# ESP.net
KiCad netlist of a schematic drawn in Altium Designer
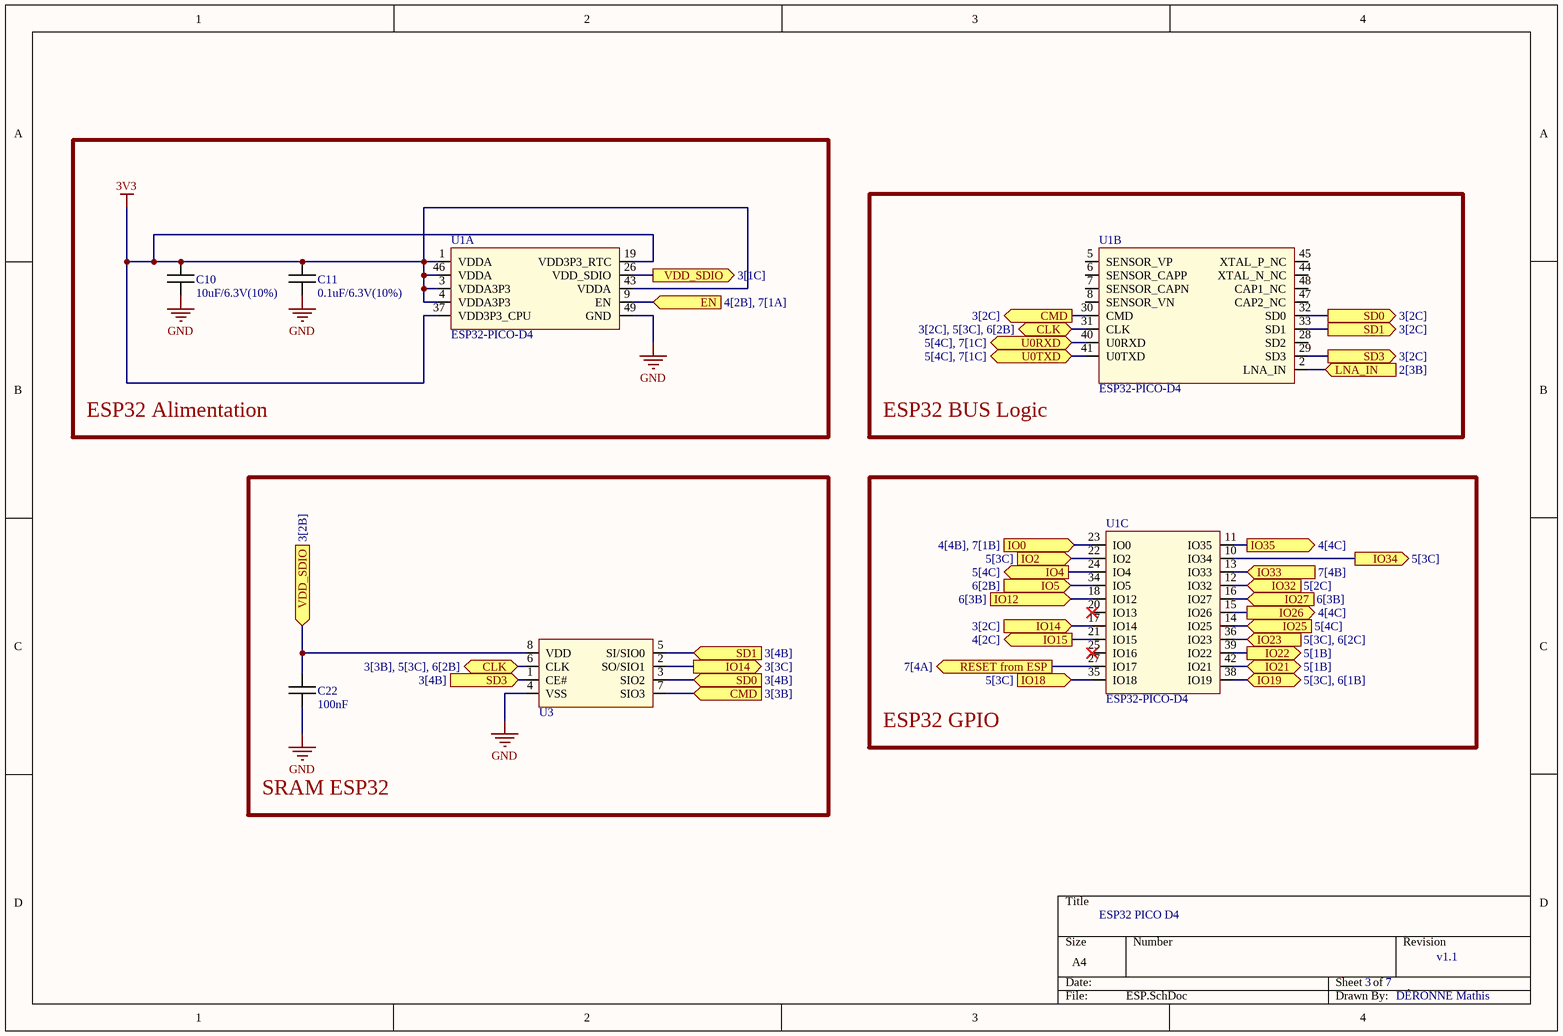
[diagram p0: ESP.SchDoc]

(export (version "E")
  (design (tool "Eeschema 10.0.6"))
  (components
    (comp (ref "C10")
      (value "10uF/6.3V(10%)")
      (footprint "CAPC1005X06N")
      (libsource (lib "SCHLibrary") (part "Capacitor"))
    )
    (comp (ref "C11")
      (value "0.1uF/6.3V(10%)")
      (footprint "CAPC1005X06N")
      (libsource (lib "SCHLibrary") (part "Capacitor"))
    )
    (comp (ref "C22")
      (value "100nF")
      (footprint "CAPC1005X06N")
      (libsource (lib "SCHLibrary") (part "Capacitor"))
    )
    (comp (ref "U1")
      (value "ESP32-PICO-D4")
      (footprint "PQFN50P700X700X104_HS-49N")
      (libsource (lib "SCHLibrary") (part "ESP32"))
    )
    (comp (ref "U3")
      (value "IS66WVS1M8BLL-104NLI")
      (footprint "SOIC127P600X175-8N")
      (description "SRAM 8Mb, SerialRAM, 2.7V-3.6V, 104MHz, 8 pin SOIC 150 mil, RoHS")
      (libsource (lib "SCHLibrary") (part "SRAM"))
    )
  )
  (nets
    (net (code "1") (name "/CLK") (class "Default")
      (node (ref "U1") (pin "31") (pinfunction "CLK_31") (pintype "passive"))
      (node (ref "U3") (pin "6") (pinfunction "CLK_6") (pintype "passive"))
    )
    (net (code "2") (name "/CMD") (class "Default")
      (node (ref "U1") (pin "30") (pinfunction "CMD_30") (pintype "passive"))
      (node (ref "U3") (pin "7") (pinfunction "SIO3_7") (pintype "passive"))
    )
    (net (code "3") (name "/EN") (class "Default")
      (node (ref "U1") (pin "9") (pinfunction "EN_9") (pintype "passive"))
    )
    (net (code "4") (name "/IO0") (class "Default")
      (node (ref "U1") (pin "23") (pinfunction "IO0_23") (pintype "passive"))
    )
    (net (code "5") (name "/IO2") (class "Default")
      (node (ref "U1") (pin "22") (pinfunction "IO2_22") (pintype "passive"))
    )
    (net (code "6") (name "/IO4") (class "Default")
      (node (ref "U1") (pin "24") (pinfunction "IO4_24") (pintype "passive"))
    )
    (net (code "7") (name "/IO5") (class "Default")
      (node (ref "U1") (pin "34") (pinfunction "IO5_34") (pintype "passive"))
    )
    (net (code "8") (name "/IO12") (class "Default")
      (node (ref "U1") (pin "18") (pinfunction "IO12_18") (pintype "passive"))
    )
    (net (code "9") (name "/IO14") (class "Default")
      (node (ref "U1") (pin "17") (pinfunction "IO14_17") (pintype "passive"))
      (node (ref "U3") (pin "2") (pinfunction "SO/SIO1_2") (pintype "passive"))
    )
    (net (code "10") (name "/IO15") (class "Default")
      (node (ref "U1") (pin "21") (pinfunction "IO15_21") (pintype "passive"))
    )
    (net (code "11") (name "/IO18") (class "Default")
      (node (ref "U1") (pin "35") (pinfunction "IO18_35") (pintype "passive"))
    )
    (net (code "12") (name "/IO19") (class "Default")
      (node (ref "U1") (pin "38") (pinfunction "IO19_38") (pintype "passive"))
    )
    (net (code "13") (name "/IO21") (class "Default")
      (node (ref "U1") (pin "42") (pinfunction "IO21_42") (pintype "passive"))
    )
    (net (code "14") (name "/IO22") (class "Default")
      (node (ref "U1") (pin "39") (pinfunction "IO22_39") (pintype "passive"))
    )
    (net (code "15") (name "/IO23") (class "Default")
      (node (ref "U1") (pin "36") (pinfunction "IO23_36") (pintype "passive"))
    )
    (net (code "16") (name "/IO25") (class "Default")
      (node (ref "U1") (pin "14") (pinfunction "IO25_14") (pintype "passive"))
    )
    (net (code "17") (name "/IO26") (class "Default")
      (node (ref "U1") (pin "15") (pinfunction "IO26_15") (pintype "passive"))
    )
    (net (code "18") (name "/IO27") (class "Default")
      (node (ref "U1") (pin "16") (pinfunction "IO27_16") (pintype "passive"))
    )
    (net (code "19") (name "/IO32") (class "Default")
      (node (ref "U1") (pin "12") (pinfunction "IO32_12") (pintype "passive"))
    )
    (net (code "20") (name "/IO33") (class "Default")
      (node (ref "U1") (pin "13") (pinfunction "IO33_13") (pintype "passive"))
    )
    (net (code "21") (name "/IO34") (class "Default")
      (node (ref "U1") (pin "10") (pinfunction "IO34_10") (pintype "passive"))
    )
    (net (code "22") (name "/IO35") (class "Default")
      (node (ref "U1") (pin "11") (pinfunction "IO35_11") (pintype "passive"))
    )
    (net (code "23") (name "/LNA_IN") (class "Default")
      (node (ref "U1") (pin "2") (pinfunction "LNA_IN_2") (pintype "passive"))
    )
    (net (code "24") (name "/RESET from ESP") (class "Default")
      (node (ref "U1") (pin "27") (pinfunction "IO17_27") (pintype "passive"))
    )
    (net (code "25") (name "/SD0") (class "Default")
      (node (ref "U1") (pin "32") (pinfunction "SD0_32") (pintype "passive"))
      (node (ref "U3") (pin "3") (pinfunction "SIO2_3") (pintype "passive"))
    )
    (net (code "26") (name "/SD1") (class "Default")
      (node (ref "U1") (pin "33") (pinfunction "SD1_33") (pintype "passive"))
      (node (ref "U3") (pin "5") (pinfunction "SI/SIO0_5") (pintype "passive"))
    )
    (net (code "27") (name "/SD3") (class "Default")
      (node (ref "U1") (pin "29") (pinfunction "SD3_29") (pintype "passive"))
      (node (ref "U3") (pin "1") (pinfunction "CE#_1") (pintype "passive"))
    )
    (net (code "28") (name "/U0RXD") (class "Default")
      (node (ref "U1") (pin "40") (pinfunction "U0RXD_40") (pintype "passive"))
    )
    (net (code "29") (name "/U0TXD") (class "Default")
      (node (ref "U1") (pin "41") (pinfunction "U0TXD_41") (pintype "passive"))
    )
    (net (code "30") (name "/VDD_SDIO") (class "Default")
      (node (ref "C22") (pin "1") (pinfunction "1_1") (pintype "passive"))
      (node (ref "U1") (pin "26") (pinfunction "VDD_SDIO_26") (pintype "passive"))
      (node (ref "U3") (pin "8") (pinfunction "VDD_8") (pintype "passive"))
    )
    (net (code "31") (name "3V3") (class "Default")
      (node (ref "C10") (pin "2") (pinfunction "2_2") (pintype "passive"))
      (node (ref "C11") (pin "2") (pinfunction "2_2") (pintype "passive"))
      (node (ref "U1") (pin "1") (pinfunction "VDDA_1") (pintype "passive"))
      (node (ref "U1") (pin "19") (pinfunction "VDD3P3_RTC_19") (pintype "passive"))
      (node (ref "U1") (pin "3") (pinfunction "VDDA3P3_3") (pintype "passive"))
      (node (ref "U1") (pin "37") (pinfunction "VDD3P3_CPU_37") (pintype "passive"))
      (node (ref "U1") (pin "4") (pinfunction "VDDA3P3_4") (pintype "passive"))
      (node (ref "U1") (pin "43") (pinfunction "VDDA_43") (pintype "passive"))
      (node (ref "U1") (pin "46") (pinfunction "VDDA_46") (pintype "passive"))
    )
    (net (code "32") (name "GND") (class "Default")
      (node (ref "C10") (pin "1") (pinfunction "1_1") (pintype "passive"))
      (node (ref "C11") (pin "1") (pinfunction "1_1") (pintype "passive"))
      (node (ref "C22") (pin "2") (pinfunction "2_2") (pintype "passive"))
      (node (ref "U1") (pin "49") (pinfunction "GND_49") (pintype "passive"))
      (node (ref "U3") (pin "4") (pinfunction "VSS_4") (pintype "passive"))
    )
    (net (code "33") (name "unconnected-(U1B-CAP1_NC-Pad48)") (class "Default")
      (node (ref "U1") (pin "48") (pinfunction "CAP1_NC_48") (pintype "passive"))
    )
    (net (code "34") (name "unconnected-(U1B-CAP2_NC-Pad47)") (class "Default")
      (node (ref "U1") (pin "47") (pinfunction "CAP2_NC_47") (pintype "passive"))
    )
    (net (code "35") (name "unconnected-(U1B-SD2-Pad28)") (class "Default")
      (node (ref "U1") (pin "28") (pinfunction "SD2_28") (pintype "passive"))
    )
    (net (code "36") (name "unconnected-(U1B-SENSOR_CAPN-Pad7)") (class "Default")
      (node (ref "U1") (pin "7") (pinfunction "SENSOR_CAPN_7") (pintype "passive"))
    )
    (net (code "37") (name "unconnected-(U1B-SENSOR_CAPP-Pad6)") (class "Default")
      (node (ref "U1") (pin "6") (pinfunction "SENSOR_CAPP_6") (pintype "passive"))
    )
    (net (code "38") (name "unconnected-(U1B-SENSOR_VN-Pad8)") (class "Default")
      (node (ref "U1") (pin "8") (pinfunction "SENSOR_VN_8") (pintype "passive"))
    )
    (net (code "39") (name "unconnected-(U1B-SENSOR_VP-Pad5)") (class "Default")
      (node (ref "U1") (pin "5") (pinfunction "SENSOR_VP_5") (pintype "passive"))
    )
    (net (code "40") (name "unconnected-(U1B-XTAL_N_NC-Pad44)") (class "Default")
      (node (ref "U1") (pin "44") (pinfunction "XTAL_N_NC_44") (pintype "passive"))
    )
    (net (code "41") (name "unconnected-(U1B-XTAL_P_NC-Pad45)") (class "Default")
      (node (ref "U1") (pin "45") (pinfunction "XTAL_P_NC_45") (pintype "passive"))
    )
    (net (code "42") (name "unconnected-(U1C-IO13-Pad20)") (class "Default")
      (node (ref "U1") (pin "20") (pinfunction "IO13_20") (pintype "passive+no_connect"))
    )
    (net (code "43") (name "unconnected-(U1C-IO16-Pad25)") (class "Default")
      (node (ref "U1") (pin "25") (pinfunction "IO16_25") (pintype "passive+no_connect"))
    )
  )
)
